# DAC_breakout.net
KiCad netlist of a schematic drawn in EAGLE
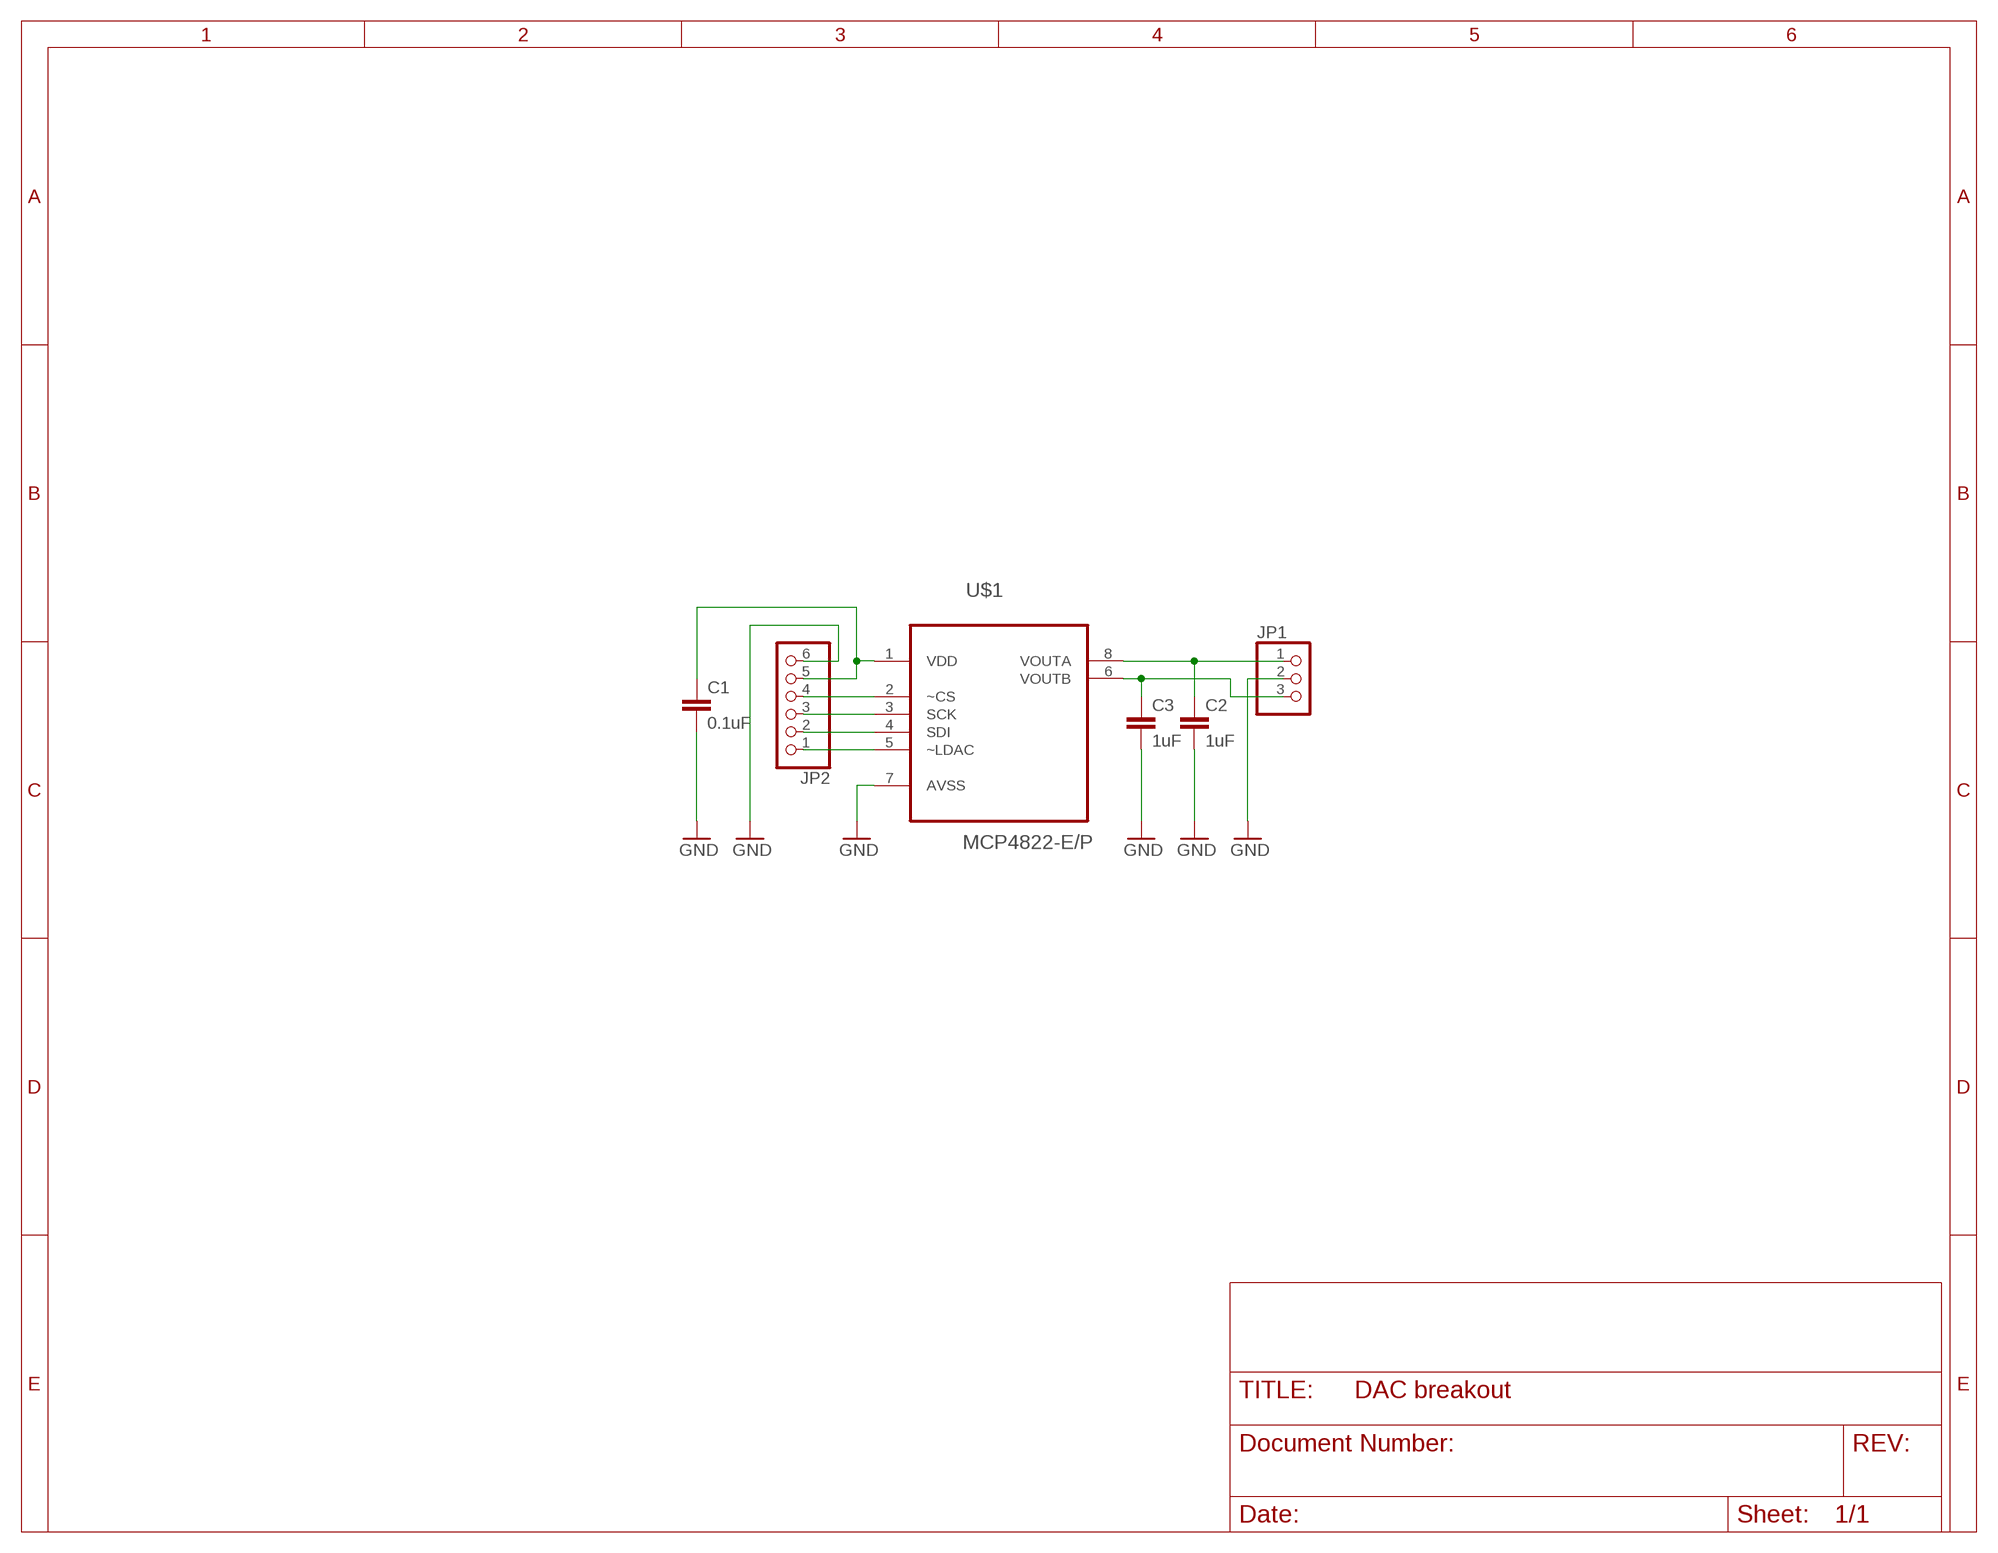
[diagram p0: schematic, sheet 1]

(export (version "E")
  (design (tool "Eeschema 10.0.6"))
  (components
    (comp (ref "C1")
      (value "0.1uF")
      (footprint "eagle-import:C025-025X050")
      (libsource (lib "eagle-import") (part "C-EU025-025X050"))
    )
    (comp (ref "C2")
      (value "1uF")
      (footprint "eagle-import:C025-025X050")
      (libsource (lib "eagle-import") (part "C-EU025-025X050"))
    )
    (comp (ref "C3")
      (value "1uF")
      (footprint "eagle-import:C025-025X050")
      (libsource (lib "eagle-import") (part "C-EU025-025X050"))
    )
    (comp (ref "JP1")
      (value "PINHD-1X3")
      (footprint "eagle-import:1X03")
      (libsource (lib "eagle-import") (part "PINHD-1X3"))
    )
    (comp (ref "JP2")
      (value "PINHD-1X6")
      (footprint "eagle-import:1X06")
      (libsource (lib "eagle-import") (part "PINHD-1X6"))
    )
    (comp (ref "U$1")
      (value "MCP4822-E/P")
      (footprint "eagle-import:DIP254P762X432-8")
      (libsource (lib "eagle-import") (part "MCP4822-E/P"))
    )
  )
  (nets
    (net (code "1") (name "GND") (class "Default")
      (node (ref "C1") (pin "2") (pinfunction "2_2") (pintype "passive"))
      (node (ref "C2") (pin "2") (pinfunction "2_2") (pintype "passive"))
      (node (ref "C3") (pin "2") (pinfunction "2_2") (pintype "passive"))
      (node (ref "JP1") (pin "2") (pinfunction "2_2") (pintype "passive"))
      (node (ref "JP2") (pin "6") (pinfunction "6_6") (pintype "passive"))
      (node (ref "U$1") (pin "7") (pinfunction "AVSS_7") (pintype "passive"))
    )
    (net (code "2") (name "Net-(U$1-SCK)") (class "Default")
      (node (ref "JP2") (pin "3") (pinfunction "3_3") (pintype "passive"))
      (node (ref "U$1") (pin "3") (pinfunction "SCK_3") (pintype "input"))
    )
    (net (code "3") (name "Net-(U$1-SDI)") (class "Default")
      (node (ref "JP2") (pin "2") (pinfunction "2_2") (pintype "passive"))
      (node (ref "U$1") (pin "4") (pinfunction "SDI_4") (pintype "input"))
    )
    (net (code "4") (name "Net-(U$1-VDD)") (class "Default")
      (node (ref "C1") (pin "1") (pinfunction "1_1") (pintype "passive"))
      (node (ref "JP2") (pin "5") (pinfunction "5_5") (pintype "passive"))
      (node (ref "U$1") (pin "1") (pinfunction "VDD_1") (pintype "power_in"))
    )
    (net (code "5") (name "Net-(U$1-VOUTA)") (class "Default")
      (node (ref "C2") (pin "1") (pinfunction "1_1") (pintype "passive"))
      (node (ref "JP1") (pin "1") (pinfunction "1_1") (pintype "passive"))
      (node (ref "U$1") (pin "8") (pinfunction "VOUTA_8") (pintype "output"))
    )
    (net (code "6") (name "Net-(U$1-VOUTB)") (class "Default")
      (node (ref "C3") (pin "1") (pinfunction "1_1") (pintype "passive"))
      (node (ref "JP1") (pin "3") (pinfunction "3_3") (pintype "passive"))
      (node (ref "U$1") (pin "6") (pinfunction "VOUTB_6") (pintype "output"))
    )
    (net (code "7") (name "Net-(U$1-~{CS})") (class "Default")
      (node (ref "JP2") (pin "4") (pinfunction "4_4") (pintype "passive"))
      (node (ref "U$1") (pin "2") (pinfunction "~{CS}_2") (pintype "input"))
    )
    (net (code "8") (name "Net-(U$1-~{LDAC})") (class "Default")
      (node (ref "JP2") (pin "1") (pinfunction "1_1") (pintype "passive"))
      (node (ref "U$1") (pin "5") (pinfunction "~{LDAC}_5") (pintype "input"))
    )
  )
)
